# Flipdot_control.net
KiCad netlist of a schematic drawn in EAGLE
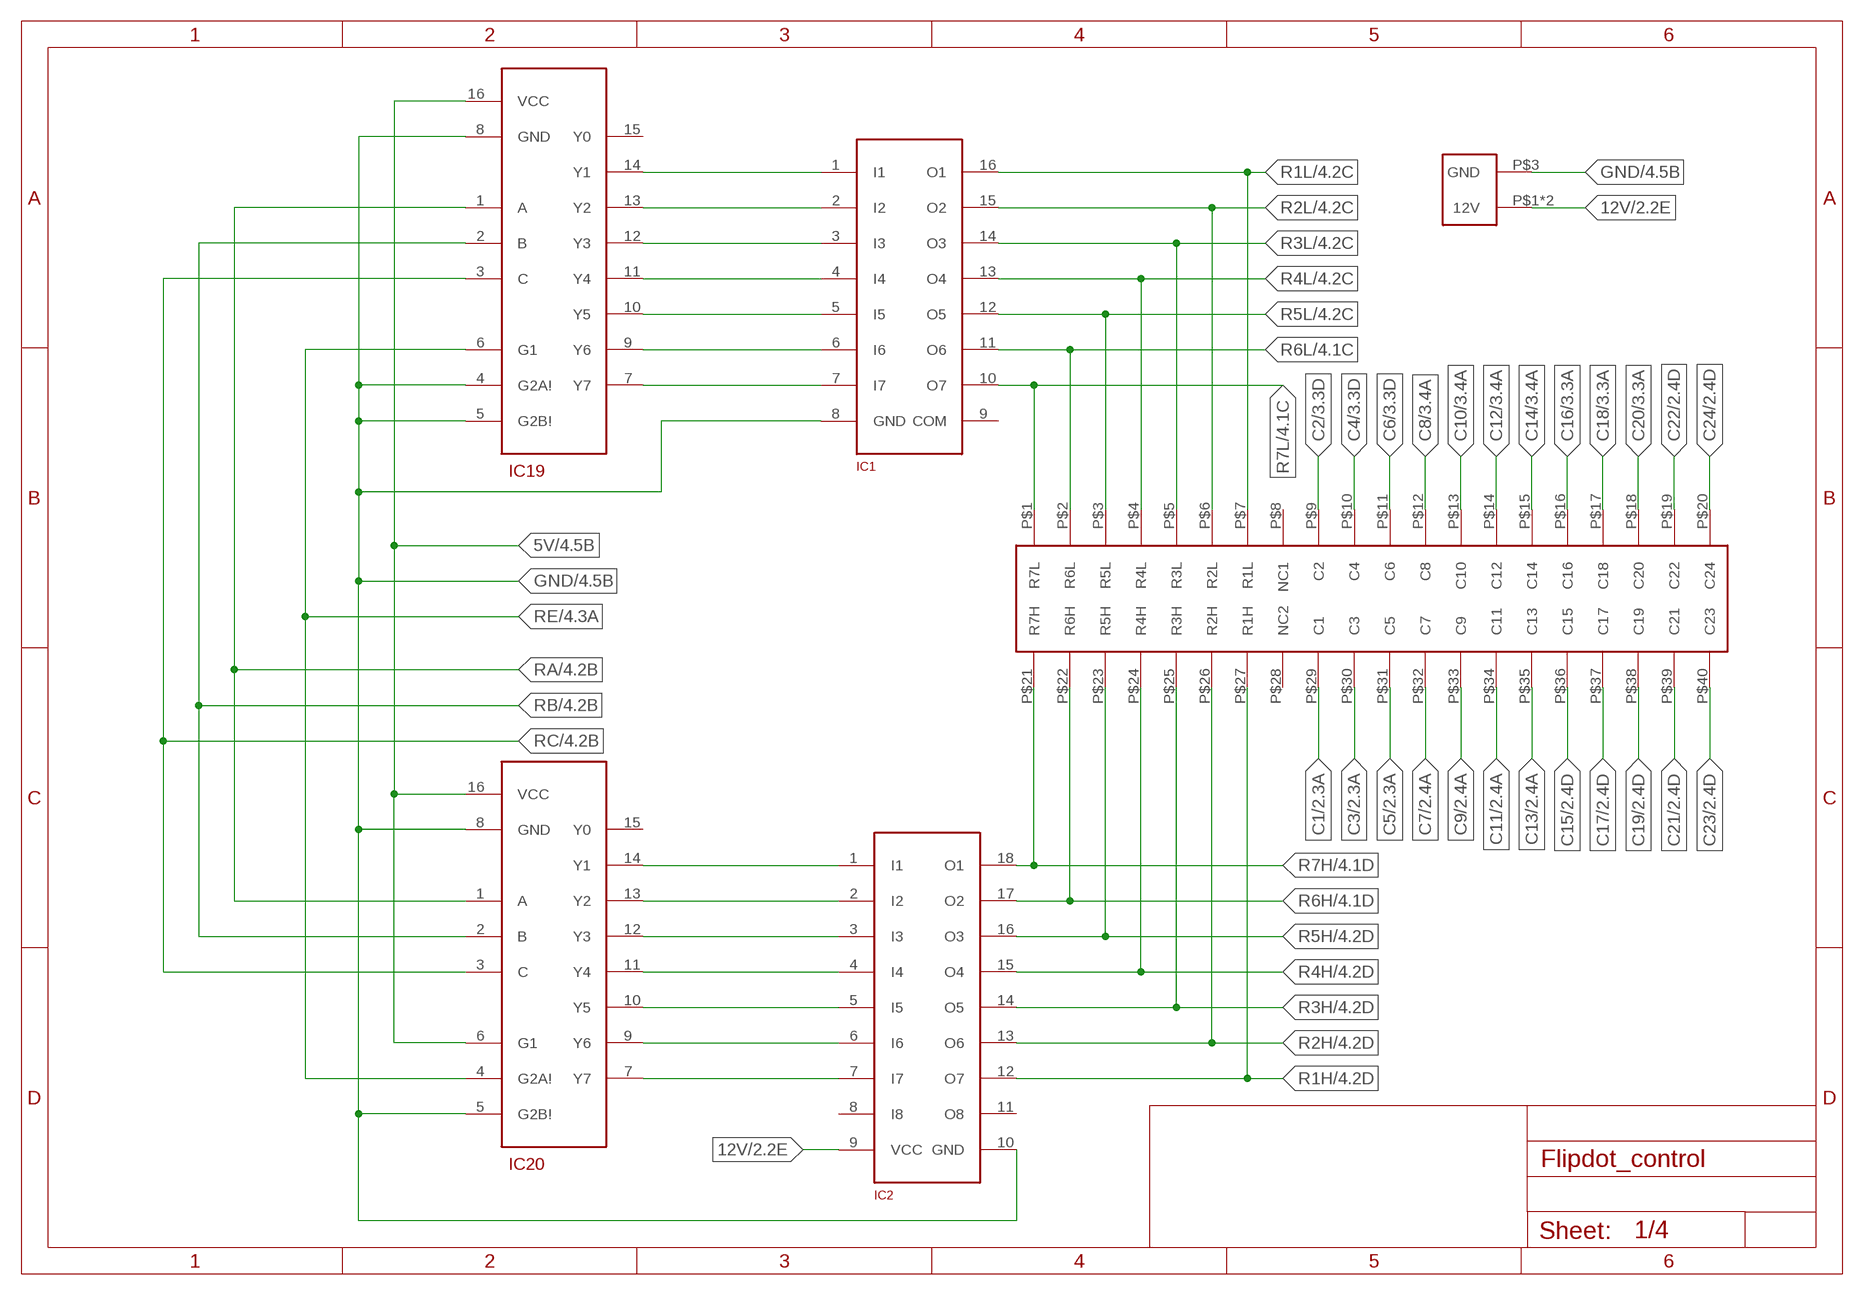
[diagram p0: schematic, sheet 1]
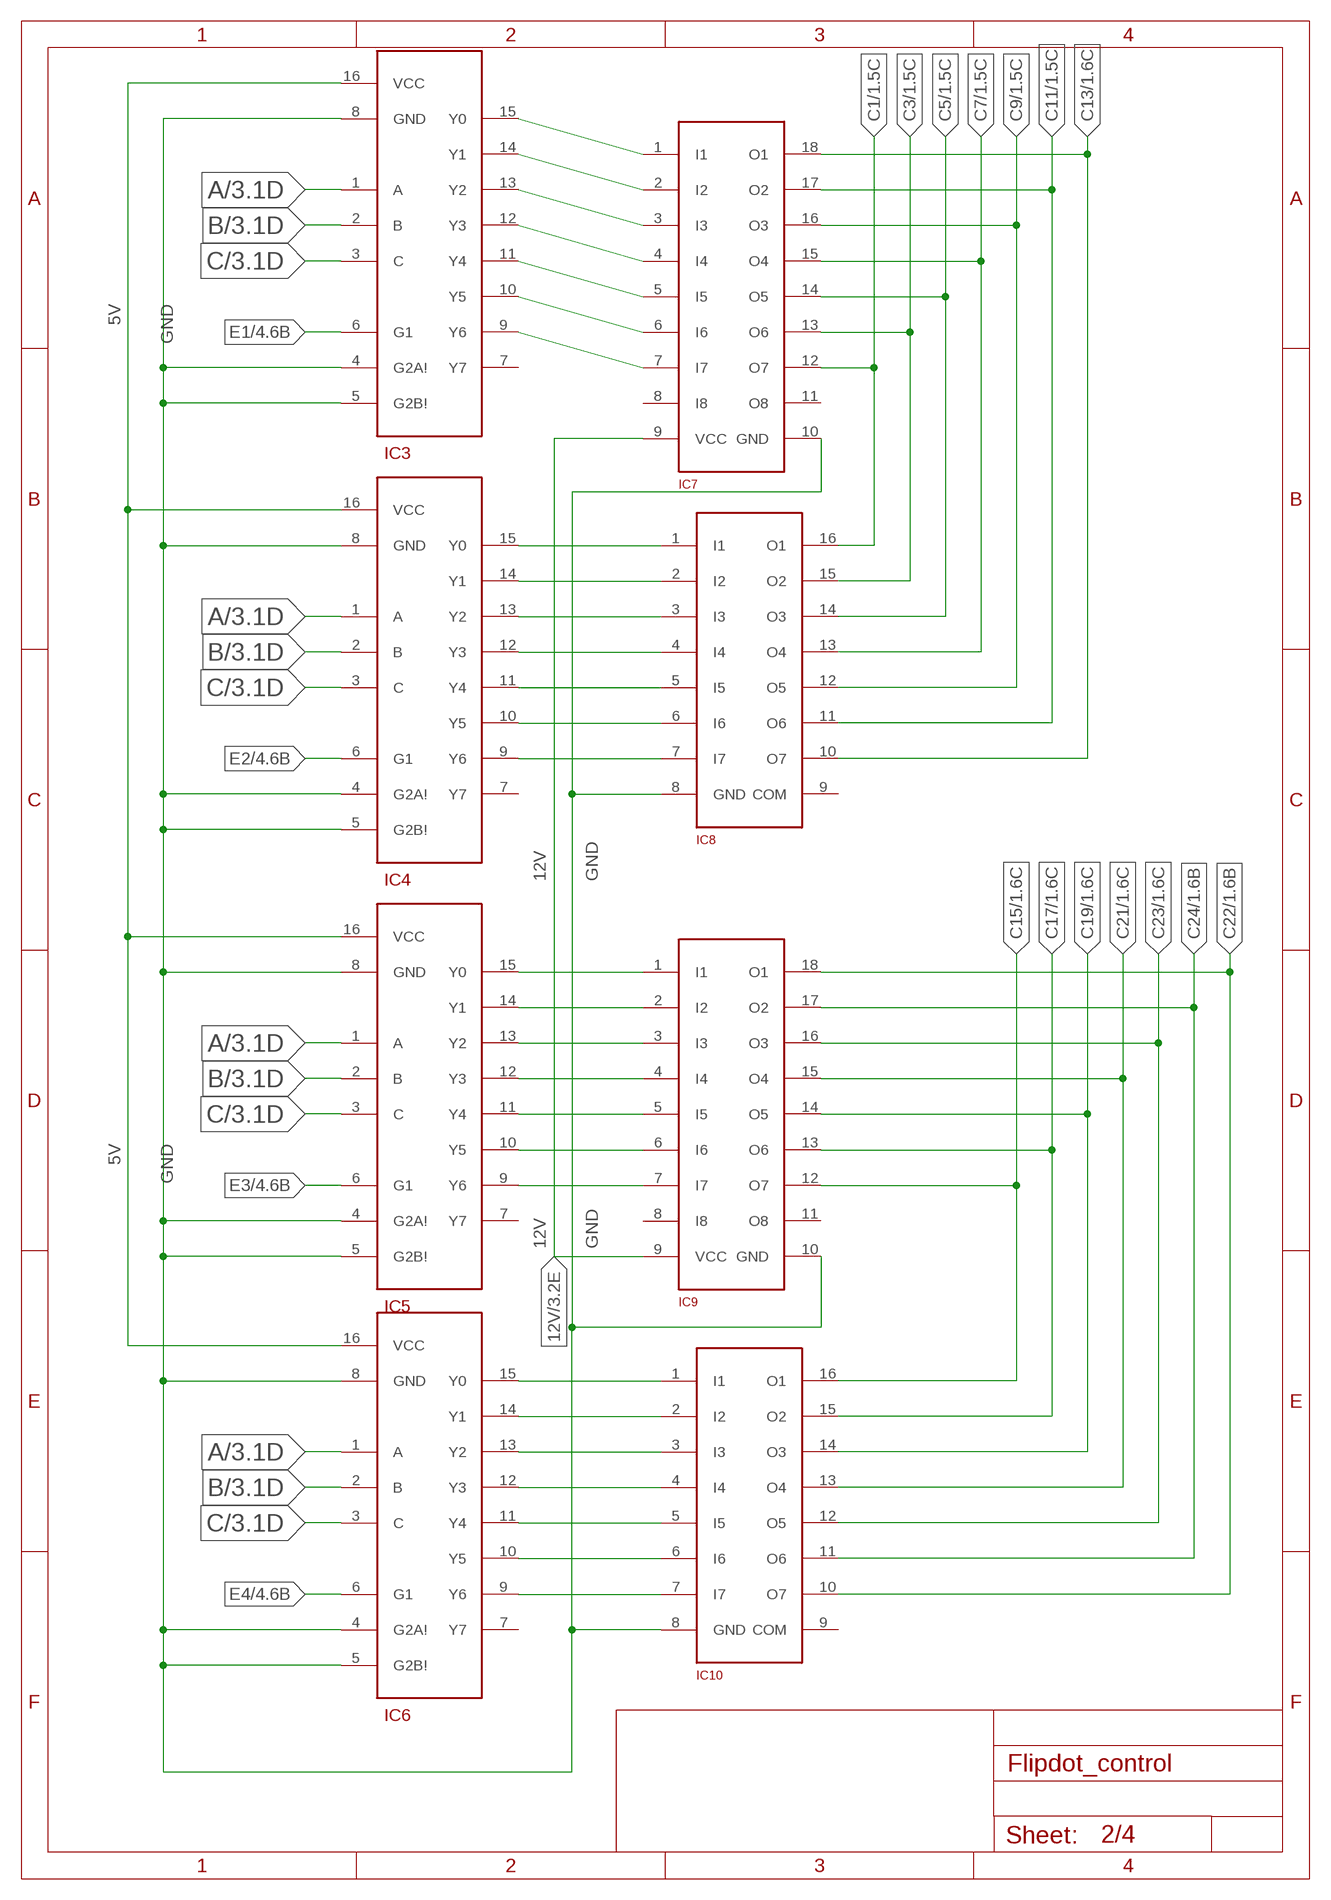
[diagram p1: schematic, sheet 2]
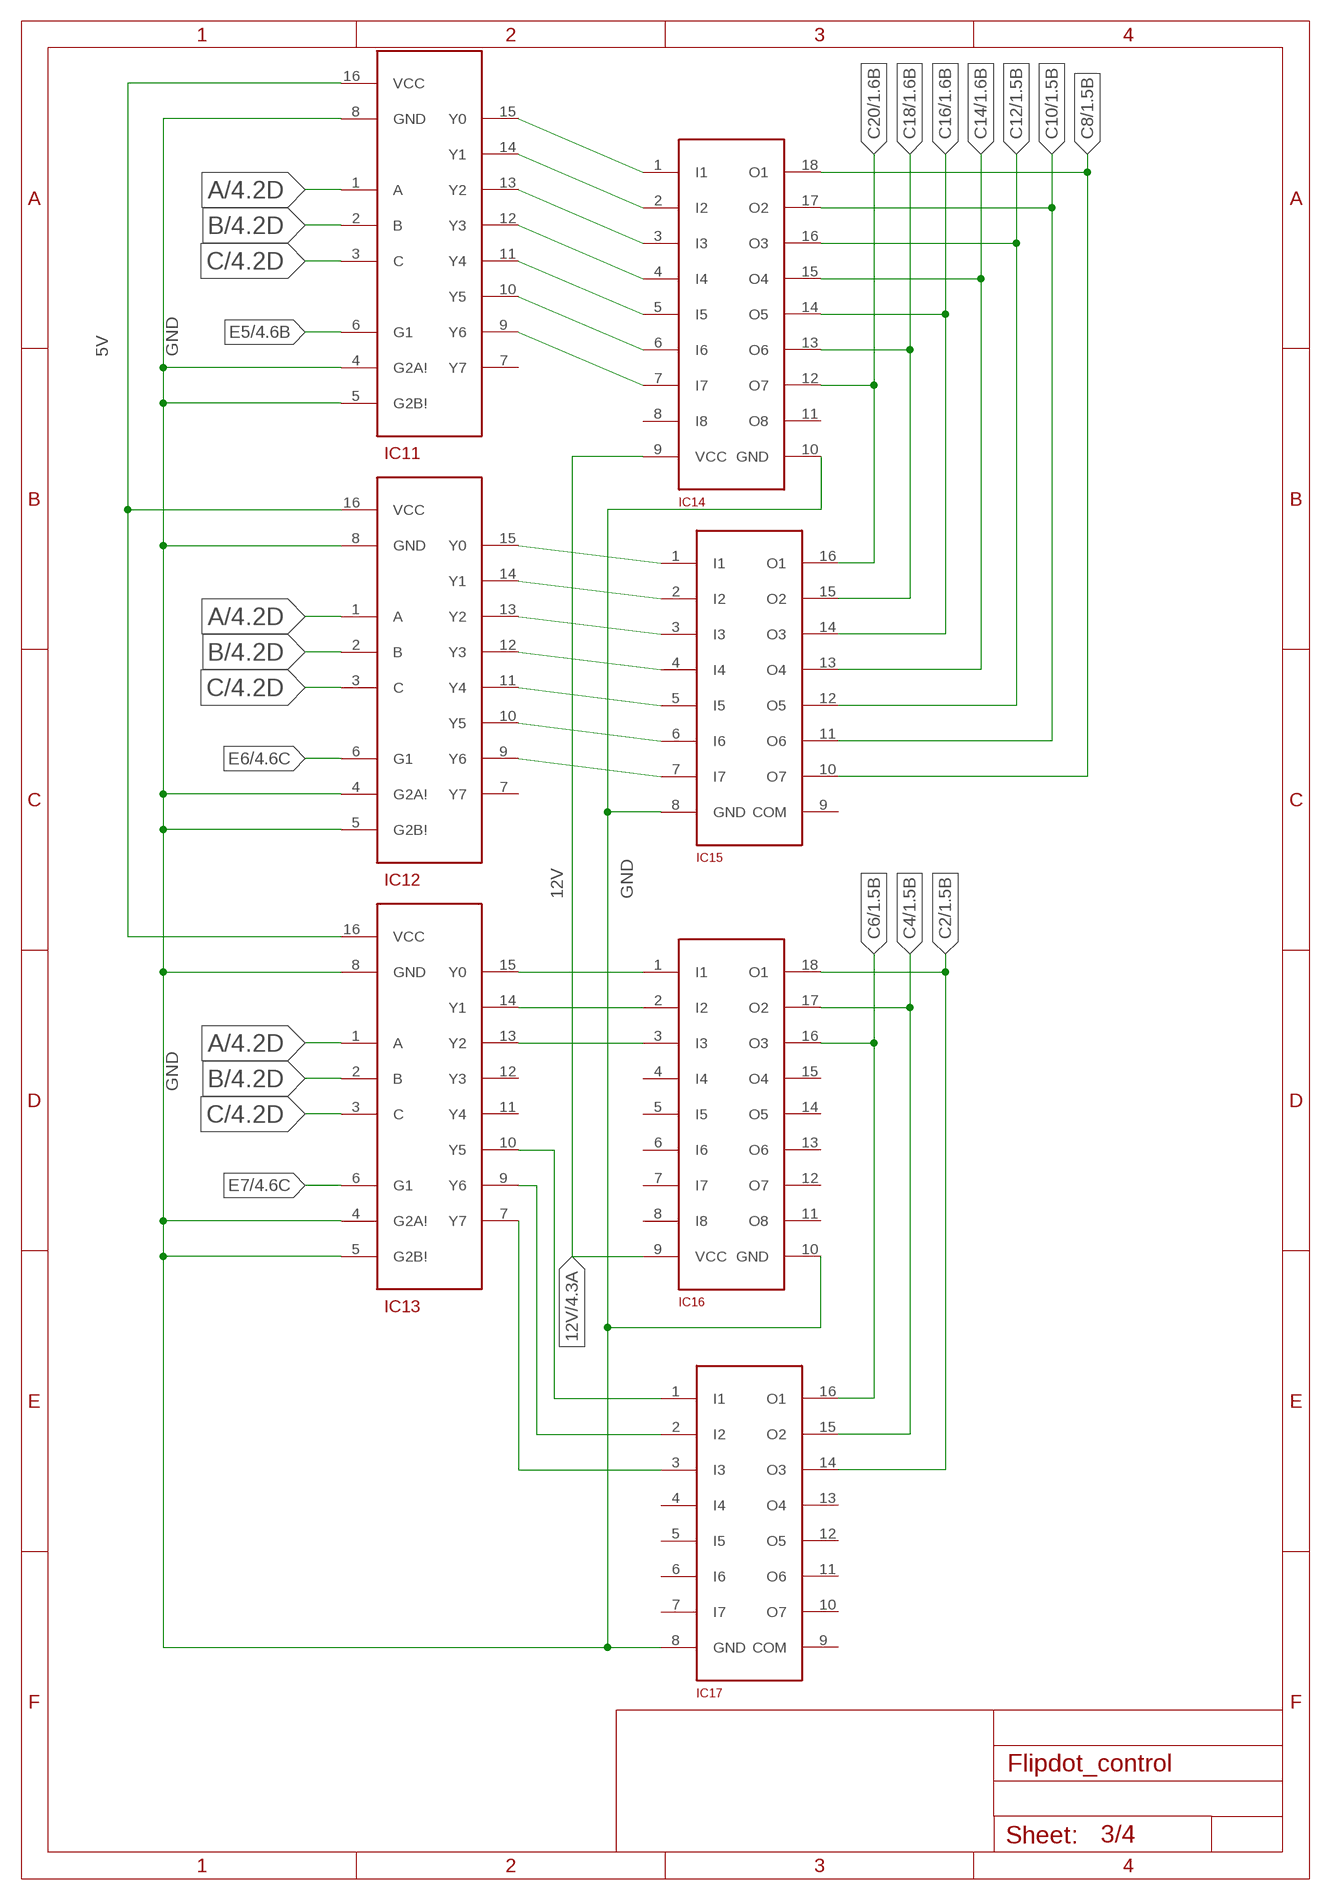
[diagram p2: schematic, sheet 3]
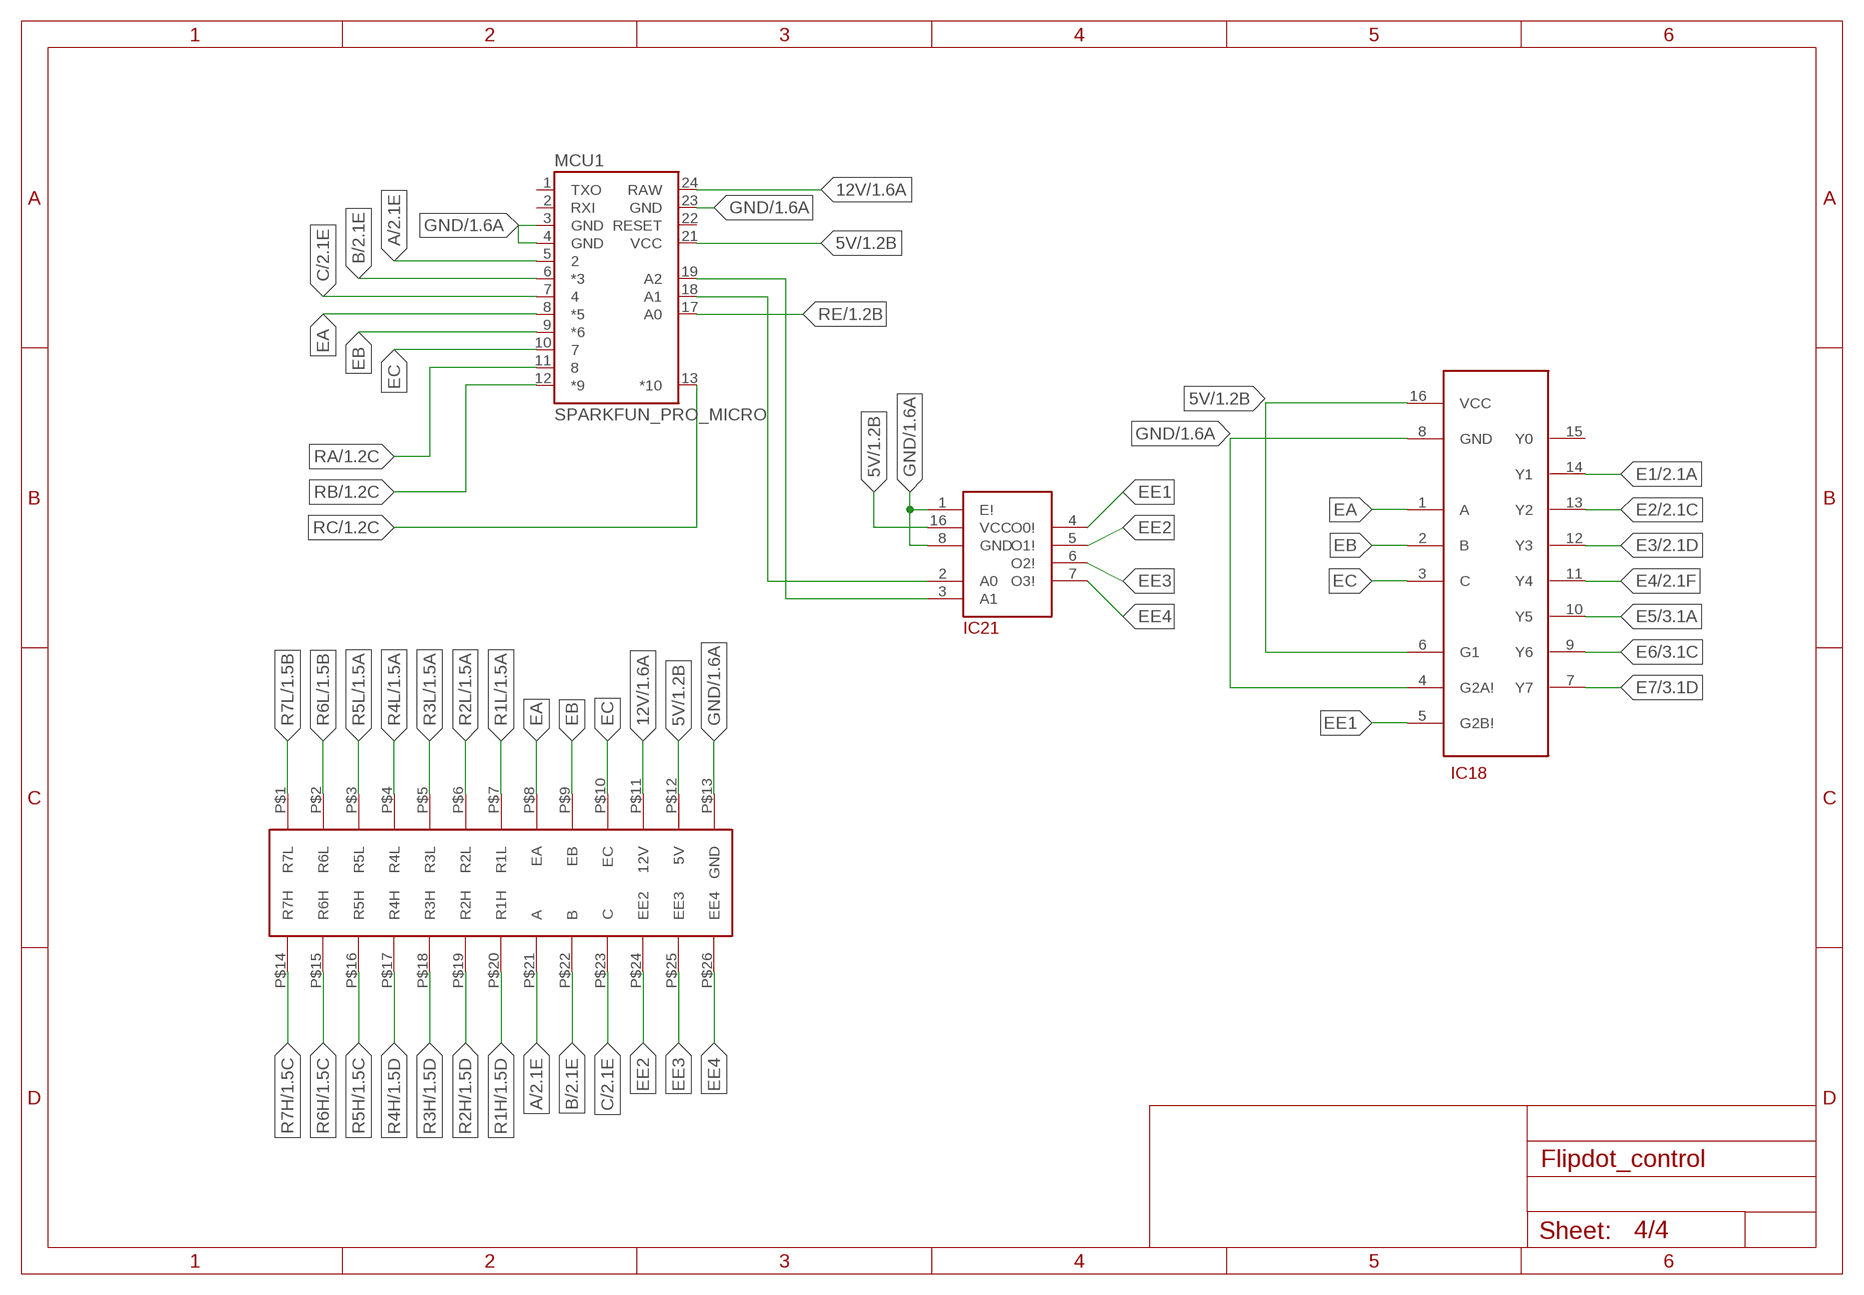
[diagram p3: schematic, sheet 4]

(export (version "E")
  (design (tool "Eeschema 10.0.6"))
  (components
    (comp (ref "IC11")
      (value "M74HC238")
      (footprint "eagle-import:SO16")
      (libsource (lib "eagle-import") (part "M74HC238"))
    )
    (comp (ref "IC12")
      (value "M74HC238")
      (footprint "eagle-import:SO16")
      (libsource (lib "eagle-import") (part "M74HC238"))
    )
    (comp (ref "IC13")
      (value "M74HC238")
      (footprint "eagle-import:SO16")
      (libsource (lib "eagle-import") (part "M74HC238"))
    )
    (comp (ref "IC14")
      (value "TD62783_AFWG")
      (footprint "eagle-import:SO18W")
      (libsource (lib "eagle-import") (part "TD62783_AFWG"))
    )
    (comp (ref "IC15")
      (value "ULN2003")
      (footprint "eagle-import:SO16")
      (libsource (lib "eagle-import") (part "ULN2003"))
    )
    (comp (ref "IC16")
      (value "TD62783_AFWG")
      (footprint "eagle-import:SO18W")
      (libsource (lib "eagle-import") (part "TD62783_AFWG"))
    )
    (comp (ref "IC17")
      (value "ULN2003")
      (footprint "eagle-import:SO16")
      (libsource (lib "eagle-import") (part "ULN2003"))
    )
    (comp (ref "IC1")
      (value "ULN2003")
      (footprint "eagle-import:SO16")
      (libsource (lib "eagle-import") (part "ULN2003"))
    )
    (comp (ref "IC2")
      (value "TD62783_AFWG")
      (footprint "eagle-import:SO18W")
      (libsource (lib "eagle-import") (part "TD62783_AFWG"))
    )
    (comp (ref "IC19")
      (value "M74HC238")
      (footprint "eagle-import:SO16")
      (libsource (lib "eagle-import") (part "M74HC238"))
    )
    (comp (ref "IC20")
      (value "M74HC238")
      (footprint "eagle-import:SO16")
      (libsource (lib "eagle-import") (part "M74HC238"))
    )
    (comp (ref "J1")
      (value "HEADER_40")
      (footprint "eagle-import:HEADER_40")
      (libsource (lib "eagle-import") (part "HEADER_40"))
    )
    (comp (ref "U$1") (value "PS") (footprint "eagle-import:PS") (libsource (lib "eagle-import") (part "PS")))
    (comp (ref "IC18")
      (value "M74HC238")
      (footprint "eagle-import:SO16")
      (libsource (lib "eagle-import") (part "M74HC238"))
    )
    (comp (ref "IC21")
      (value "74AC139SC")
      (footprint "eagle-import:SO16")
      (libsource (lib "eagle-import") (part "74AC139SC"))
    )
    (comp (ref "J2")
      (value "HEADER_26")
      (footprint "eagle-import:HEADER_26")
      (libsource (lib "eagle-import") (part "HEADER_26"))
    )
    (comp (ref "MCU1")
      (value "SPARKFUN_PRO_MICRO")
      (footprint "eagle-import:SPARKFUN_PRO_MICRO")
      (libsource (lib "eagle-import") (part "SPARKFUN_PRO_MICRO"))
    )
    (comp (ref "IC3")
      (value "M74HC238")
      (footprint "eagle-import:SO16")
      (libsource (lib "eagle-import") (part "M74HC238"))
    )
    (comp (ref "IC4")
      (value "M74HC238")
      (footprint "eagle-import:SO16")
      (libsource (lib "eagle-import") (part "M74HC238"))
    )
    (comp (ref "IC5")
      (value "M74HC238")
      (footprint "eagle-import:SO16")
      (libsource (lib "eagle-import") (part "M74HC238"))
    )
    (comp (ref "IC6")
      (value "M74HC238")
      (footprint "eagle-import:SO16")
      (libsource (lib "eagle-import") (part "M74HC238"))
    )
    (comp (ref "IC7")
      (value "TD62783_AFWG")
      (footprint "eagle-import:SO18W")
      (libsource (lib "eagle-import") (part "TD62783_AFWG"))
    )
    (comp (ref "IC8")
      (value "ULN2003")
      (footprint "eagle-import:SO16")
      (libsource (lib "eagle-import") (part "ULN2003"))
    )
    (comp (ref "IC9")
      (value "TD62783_AFWG")
      (footprint "eagle-import:SO18W")
      (libsource (lib "eagle-import") (part "TD62783_AFWG"))
    )
    (comp (ref "IC10")
      (value "ULN2003")
      (footprint "eagle-import:SO16")
      (libsource (lib "eagle-import") (part "ULN2003"))
    )
  )
  (nets
    (net (code "1") (name "5V") (class "Default")
      (node (ref "IC11") (pin "16") (pinfunction "VCC_16") (pintype "bidirectional"))
      (node (ref "IC12") (pin "16") (pinfunction "VCC_16") (pintype "bidirectional"))
      (node (ref "IC13") (pin "16") (pinfunction "VCC_16") (pintype "bidirectional"))
      (node (ref "IC18") (pin "16") (pinfunction "VCC_16") (pintype "bidirectional"))
      (node (ref "IC18") (pin "6") (pinfunction "G1_6") (pintype "bidirectional"))
      (node (ref "IC19") (pin "16") (pinfunction "VCC_16") (pintype "bidirectional"))
      (node (ref "IC20") (pin "16") (pinfunction "VCC_16") (pintype "bidirectional"))
      (node (ref "IC20") (pin "6") (pinfunction "G1_6") (pintype "bidirectional"))
      (node (ref "IC21") (pin "16") (pinfunction "VCC_16") (pintype "bidirectional"))
      (node (ref "IC3") (pin "16") (pinfunction "VCC_16") (pintype "bidirectional"))
      (node (ref "IC4") (pin "16") (pinfunction "VCC_16") (pintype "bidirectional"))
      (node (ref "IC5") (pin "16") (pinfunction "VCC_16") (pintype "bidirectional"))
      (node (ref "IC6") (pin "16") (pinfunction "VCC_16") (pintype "bidirectional"))
      (node (ref "J2") (pin "P$12") (pinfunction "5V_P$12") (pintype "bidirectional"))
      (node (ref "MCU1") (pin "21") (pinfunction "VCC_21") (pintype "power_in"))
    )
    (net (code "2") (name "12V") (class "Default")
      (node (ref "IC14") (pin "9") (pinfunction "VCC_9") (pintype "bidirectional"))
      (node (ref "IC16") (pin "9") (pinfunction "VCC_9") (pintype "bidirectional"))
      (node (ref "IC2") (pin "9") (pinfunction "VCC_9") (pintype "bidirectional"))
      (node (ref "IC7") (pin "9") (pinfunction "VCC_9") (pintype "bidirectional"))
      (node (ref "IC9") (pin "9") (pinfunction "VCC_9") (pintype "bidirectional"))
      (node (ref "J2") (pin "P$11") (pinfunction "12V_P$11") (pintype "bidirectional"))
      (node (ref "MCU1") (pin "24") (pinfunction "RAW_24") (pintype "power_in"))
      (node (ref "U$1") (pin "P$1") (pinfunction "12V_P$1") (pintype "bidirectional"))
      (node (ref "U$1") (pin "P$2") (pinfunction "12V_P$2") (pintype "bidirectional"))
    )
    (net (code "3") (name "A") (class "Default")
      (node (ref "IC11") (pin "1") (pinfunction "A_1") (pintype "bidirectional"))
      (node (ref "IC12") (pin "1") (pinfunction "A_1") (pintype "bidirectional"))
      (node (ref "IC13") (pin "1") (pinfunction "A_1") (pintype "bidirectional"))
      (node (ref "IC3") (pin "1") (pinfunction "A_1") (pintype "bidirectional"))
      (node (ref "IC4") (pin "1") (pinfunction "A_1") (pintype "bidirectional"))
      (node (ref "IC5") (pin "1") (pinfunction "A_1") (pintype "bidirectional"))
      (node (ref "IC6") (pin "1") (pinfunction "A_1") (pintype "bidirectional"))
      (node (ref "J2") (pin "P$21") (pinfunction "A_P$21") (pintype "bidirectional"))
      (node (ref "MCU1") (pin "5") (pinfunction "2_5") (pintype "bidirectional"))
    )
    (net (code "4") (name "B") (class "Default")
      (node (ref "IC11") (pin "2") (pinfunction "B_2") (pintype "bidirectional"))
      (node (ref "IC12") (pin "2") (pinfunction "B_2") (pintype "bidirectional"))
      (node (ref "IC13") (pin "2") (pinfunction "B_2") (pintype "bidirectional"))
      (node (ref "IC3") (pin "2") (pinfunction "B_2") (pintype "bidirectional"))
      (node (ref "IC4") (pin "2") (pinfunction "B_2") (pintype "bidirectional"))
      (node (ref "IC5") (pin "2") (pinfunction "B_2") (pintype "bidirectional"))
      (node (ref "IC6") (pin "2") (pinfunction "B_2") (pintype "bidirectional"))
      (node (ref "J2") (pin "P$22") (pinfunction "B_P$22") (pintype "bidirectional"))
      (node (ref "MCU1") (pin "6") (pinfunction "*3_6") (pintype "bidirectional"))
    )
    (net (code "5") (name "C") (class "Default")
      (node (ref "IC11") (pin "3") (pinfunction "C_3") (pintype "bidirectional"))
      (node (ref "IC12") (pin "3") (pinfunction "C_3") (pintype "bidirectional"))
      (node (ref "IC13") (pin "3") (pinfunction "C_3") (pintype "bidirectional"))
      (node (ref "IC3") (pin "3") (pinfunction "C_3") (pintype "bidirectional"))
      (node (ref "IC4") (pin "3") (pinfunction "C_3") (pintype "bidirectional"))
      (node (ref "IC5") (pin "3") (pinfunction "C_3") (pintype "bidirectional"))
      (node (ref "IC6") (pin "3") (pinfunction "C_3") (pintype "bidirectional"))
      (node (ref "J2") (pin "P$23") (pinfunction "C_P$23") (pintype "bidirectional"))
      (node (ref "MCU1") (pin "7") (pinfunction "4_7") (pintype "bidirectional"))
    )
    (net (code "6") (name "C1") (class "Default")
      (node (ref "IC7") (pin "12") (pinfunction "O7_12") (pintype "bidirectional"))
      (node (ref "IC8") (pin "16") (pinfunction "O1_16") (pintype "bidirectional"))
      (node (ref "J1") (pin "P$29") (pinfunction "C1_P$29") (pintype "bidirectional"))
    )
    (net (code "7") (name "C2") (class "Default")
      (node (ref "IC16") (pin "18") (pinfunction "O1_18") (pintype "bidirectional"))
      (node (ref "IC17") (pin "14") (pinfunction "O3_14") (pintype "bidirectional"))
      (node (ref "J1") (pin "P$9") (pinfunction "C2_P$9") (pintype "bidirectional"))
    )
    (net (code "8") (name "C3") (class "Default")
      (node (ref "IC7") (pin "13") (pinfunction "O6_13") (pintype "bidirectional"))
      (node (ref "IC8") (pin "15") (pinfunction "O2_15") (pintype "bidirectional"))
      (node (ref "J1") (pin "P$30") (pinfunction "C3_P$30") (pintype "bidirectional"))
    )
    (net (code "9") (name "C4") (class "Default")
      (node (ref "IC16") (pin "17") (pinfunction "O2_17") (pintype "bidirectional"))
      (node (ref "IC17") (pin "15") (pinfunction "O2_15") (pintype "bidirectional"))
      (node (ref "J1") (pin "P$10") (pinfunction "C4_P$10") (pintype "bidirectional"))
    )
    (net (code "10") (name "C5") (class "Default")
      (node (ref "IC7") (pin "14") (pinfunction "O5_14") (pintype "bidirectional"))
      (node (ref "IC8") (pin "14") (pinfunction "O3_14") (pintype "bidirectional"))
      (node (ref "J1") (pin "P$31") (pinfunction "C5_P$31") (pintype "bidirectional"))
    )
    (net (code "11") (name "C6") (class "Default")
      (node (ref "IC16") (pin "16") (pinfunction "O3_16") (pintype "bidirectional"))
      (node (ref "IC17") (pin "16") (pinfunction "O1_16") (pintype "bidirectional"))
      (node (ref "J1") (pin "P$11") (pinfunction "C6_P$11") (pintype "bidirectional"))
    )
    (net (code "12") (name "C7") (class "Default")
      (node (ref "IC7") (pin "15") (pinfunction "O4_15") (pintype "bidirectional"))
      (node (ref "IC8") (pin "13") (pinfunction "O4_13") (pintype "bidirectional"))
      (node (ref "J1") (pin "P$32") (pinfunction "C7_P$32") (pintype "bidirectional"))
    )
    (net (code "13") (name "C8") (class "Default")
      (node (ref "IC14") (pin "18") (pinfunction "O1_18") (pintype "bidirectional"))
      (node (ref "IC15") (pin "10") (pinfunction "O7_10") (pintype "bidirectional"))
      (node (ref "J1") (pin "P$12") (pinfunction "C8_P$12") (pintype "bidirectional"))
    )
    (net (code "14") (name "C9") (class "Default")
      (node (ref "IC7") (pin "16") (pinfunction "O3_16") (pintype "bidirectional"))
      (node (ref "IC8") (pin "12") (pinfunction "O5_12") (pintype "bidirectional"))
      (node (ref "J1") (pin "P$33") (pinfunction "C9_P$33") (pintype "bidirectional"))
    )
    (net (code "15") (name "C10") (class "Default")
      (node (ref "IC14") (pin "17") (pinfunction "O2_17") (pintype "bidirectional"))
      (node (ref "IC15") (pin "11") (pinfunction "O6_11") (pintype "bidirectional"))
      (node (ref "J1") (pin "P$13") (pinfunction "C10_P$13") (pintype "bidirectional"))
    )
    (net (code "16") (name "C11") (class "Default")
      (node (ref "IC7") (pin "17") (pinfunction "O2_17") (pintype "bidirectional"))
      (node (ref "IC8") (pin "11") (pinfunction "O6_11") (pintype "bidirectional"))
      (node (ref "J1") (pin "P$34") (pinfunction "C11_P$34") (pintype "bidirectional"))
    )
    (net (code "17") (name "C12") (class "Default")
      (node (ref "IC14") (pin "16") (pinfunction "O3_16") (pintype "bidirectional"))
      (node (ref "IC15") (pin "12") (pinfunction "O5_12") (pintype "bidirectional"))
      (node (ref "J1") (pin "P$14") (pinfunction "C12_P$14") (pintype "bidirectional"))
    )
    (net (code "18") (name "C13") (class "Default")
      (node (ref "IC7") (pin "18") (pinfunction "O1_18") (pintype "bidirectional"))
      (node (ref "IC8") (pin "10") (pinfunction "O7_10") (pintype "bidirectional"))
      (node (ref "J1") (pin "P$35") (pinfunction "C13_P$35") (pintype "bidirectional"))
    )
    (net (code "19") (name "C14") (class "Default")
      (node (ref "IC14") (pin "15") (pinfunction "O4_15") (pintype "bidirectional"))
      (node (ref "IC15") (pin "13") (pinfunction "O4_13") (pintype "bidirectional"))
      (node (ref "J1") (pin "P$15") (pinfunction "C14_P$15") (pintype "bidirectional"))
    )
    (net (code "20") (name "C15") (class "Default")
      (node (ref "IC10") (pin "16") (pinfunction "O1_16") (pintype "bidirectional"))
      (node (ref "IC9") (pin "12") (pinfunction "O7_12") (pintype "bidirectional"))
      (node (ref "J1") (pin "P$36") (pinfunction "C15_P$36") (pintype "bidirectional"))
    )
    (net (code "21") (name "C16") (class "Default")
      (node (ref "IC14") (pin "14") (pinfunction "O5_14") (pintype "bidirectional"))
      (node (ref "IC15") (pin "14") (pinfunction "O3_14") (pintype "bidirectional"))
      (node (ref "J1") (pin "P$16") (pinfunction "C16_P$16") (pintype "bidirectional"))
    )
    (net (code "22") (name "C17") (class "Default")
      (node (ref "IC10") (pin "15") (pinfunction "O2_15") (pintype "bidirectional"))
      (node (ref "IC9") (pin "13") (pinfunction "O6_13") (pintype "bidirectional"))
      (node (ref "J1") (pin "P$37") (pinfunction "C17_P$37") (pintype "bidirectional"))
    )
    (net (code "23") (name "C18") (class "Default")
      (node (ref "IC14") (pin "13") (pinfunction "O6_13") (pintype "bidirectional"))
      (node (ref "IC15") (pin "15") (pinfunction "O2_15") (pintype "bidirectional"))
      (node (ref "J1") (pin "P$17") (pinfunction "C18_P$17") (pintype "bidirectional"))
    )
    (net (code "24") (name "C19") (class "Default")
      (node (ref "IC10") (pin "14") (pinfunction "O3_14") (pintype "bidirectional"))
      (node (ref "IC9") (pin "14") (pinfunction "O5_14") (pintype "bidirectional"))
      (node (ref "J1") (pin "P$38") (pinfunction "C19_P$38") (pintype "bidirectional"))
    )
    (net (code "25") (name "C20") (class "Default")
      (node (ref "IC14") (pin "12") (pinfunction "O7_12") (pintype "bidirectional"))
      (node (ref "IC15") (pin "16") (pinfunction "O1_16") (pintype "bidirectional"))
      (node (ref "J1") (pin "P$18") (pinfunction "C20_P$18") (pintype "bidirectional"))
    )
    (net (code "26") (name "C21") (class "Default")
      (node (ref "IC10") (pin "13") (pinfunction "O4_13") (pintype "bidirectional"))
      (node (ref "IC9") (pin "15") (pinfunction "O4_15") (pintype "bidirectional"))
      (node (ref "J1") (pin "P$39") (pinfunction "C21_P$39") (pintype "bidirectional"))
    )
    (net (code "27") (name "C22") (class "Default")
      (node (ref "IC10") (pin "10") (pinfunction "O7_10") (pintype "bidirectional"))
      (node (ref "IC9") (pin "18") (pinfunction "O1_18") (pintype "bidirectional"))
      (node (ref "J1") (pin "P$19") (pinfunction "C22_P$19") (pintype "bidirectional"))
    )
    (net (code "28") (name "C23") (class "Default")
      (node (ref "IC10") (pin "12") (pinfunction "O5_12") (pintype "bidirectional"))
      (node (ref "IC9") (pin "16") (pinfunction "O3_16") (pintype "bidirectional"))
      (node (ref "J1") (pin "P$40") (pinfunction "C23_P$40") (pintype "bidirectional"))
    )
    (net (code "29") (name "C24") (class "Default")
      (node (ref "IC10") (pin "11") (pinfunction "O6_11") (pintype "bidirectional"))
      (node (ref "IC9") (pin "17") (pinfunction "O2_17") (pintype "bidirectional"))
      (node (ref "J1") (pin "P$20") (pinfunction "C24_P$20") (pintype "bidirectional"))
    )
    (net (code "30") (name "E1") (class "Default")
      (node (ref "IC18") (pin "14") (pinfunction "Y1_14") (pintype "bidirectional"))
      (node (ref "IC3") (pin "6") (pinfunction "G1_6") (pintype "bidirectional"))
    )
    (net (code "31") (name "E2") (class "Default")
      (node (ref "IC18") (pin "13") (pinfunction "Y2_13") (pintype "bidirectional"))
      (node (ref "IC4") (pin "6") (pinfunction "G1_6") (pintype "bidirectional"))
    )
    (net (code "32") (name "E3") (class "Default")
      (node (ref "IC18") (pin "12") (pinfunction "Y3_12") (pintype "bidirectional"))
      (node (ref "IC5") (pin "6") (pinfunction "G1_6") (pintype "bidirectional"))
    )
    (net (code "33") (name "E4") (class "Default")
      (node (ref "IC18") (pin "11") (pinfunction "Y4_11") (pintype "bidirectional"))
      (node (ref "IC6") (pin "6") (pinfunction "G1_6") (pintype "bidirectional"))
    )
    (net (code "34") (name "E5") (class "Default")
      (node (ref "IC11") (pin "6") (pinfunction "G1_6") (pintype "bidirectional"))
      (node (ref "IC18") (pin "10") (pinfunction "Y5_10") (pintype "bidirectional"))
    )
    (net (code "35") (name "E6") (class "Default")
      (node (ref "IC12") (pin "6") (pinfunction "G1_6") (pintype "bidirectional"))
      (node (ref "IC18") (pin "9") (pinfunction "Y6_9") (pintype "bidirectional"))
    )
    (net (code "36") (name "E7") (class "Default")
      (node (ref "IC13") (pin "6") (pinfunction "G1_6") (pintype "bidirectional"))
      (node (ref "IC18") (pin "7") (pinfunction "Y7_7") (pintype "bidirectional"))
    )
    (net (code "37") (name "EA") (class "Default")
      (node (ref "IC18") (pin "1") (pinfunction "A_1") (pintype "bidirectional"))
      (node (ref "J2") (pin "P$8") (pinfunction "EA_P$8") (pintype "bidirectional"))
      (node (ref "MCU1") (pin "8") (pinfunction "*5_8") (pintype "bidirectional"))
    )
    (net (code "38") (name "EB") (class "Default")
      (node (ref "IC18") (pin "2") (pinfunction "B_2") (pintype "bidirectional"))
      (node (ref "J2") (pin "P$9") (pinfunction "EB_P$9") (pintype "bidirectional"))
      (node (ref "MCU1") (pin "9") (pinfunction "*6_9") (pintype "bidirectional"))
    )
    (net (code "39") (name "EC") (class "Default")
      (node (ref "IC18") (pin "3") (pinfunction "C_3") (pintype "bidirectional"))
      (node (ref "J2") (pin "P$10") (pinfunction "EC_P$10") (pintype "bidirectional"))
      (node (ref "MCU1") (pin "10") (pinfunction "7_10") (pintype "bidirectional"))
    )
    (net (code "40") (name "EE1") (class "Default")
      (node (ref "IC18") (pin "5") (pinfunction "G2B~{}_5") (pintype "bidirectional"))
      (node (ref "IC21") (pin "4") (pinfunction "O0~{}_4") (pintype "bidirectional"))
    )
    (net (code "41") (name "EE2") (class "Default")
      (node (ref "IC21") (pin "5") (pinfunction "O1~{}_5") (pintype "bidirectional"))
      (node (ref "J2") (pin "P$24") (pinfunction "EE2_P$24") (pintype "bidirectional"))
    )
    (net (code "42") (name "EE3") (class "Default")
      (node (ref "IC21") (pin "6") (pinfunction "O2~{}_6") (pintype "bidirectional"))
      (node (ref "J2") (pin "P$25") (pinfunction "EE3_P$25") (pintype "bidirectional"))
    )
    (net (code "43") (name "EE4") (class "Default")
      (node (ref "IC21") (pin "7") (pinfunction "O3~{}_7") (pintype "bidirectional"))
      (node (ref "J2") (pin "P$26") (pinfunction "EE4_P$26") (pintype "bidirectional"))
    )
    (net (code "44") (name "GND") (class "Default")
      (node (ref "IC1") (pin "8") (pinfunction "GND_8") (pintype "bidirectional"))
      (node (ref "IC10") (pin "8") (pinfunction "GND_8") (pintype "bidirectional"))
      (node (ref "IC11") (pin "4") (pinfunction "G2A~{}_4") (pintype "bidirectional"))
      (node (ref "IC11") (pin "5") (pinfunction "G2B~{}_5") (pintype "bidirectional"))
      (node (ref "IC11") (pin "8") (pinfunction "GND_8") (pintype "bidirectional"))
      (node (ref "IC12") (pin "4") (pinfunction "G2A~{}_4") (pintype "bidirectional"))
      (node (ref "IC12") (pin "5") (pinfunction "G2B~{}_5") (pintype "bidirectional"))
      (node (ref "IC12") (pin "8") (pinfunction "GND_8") (pintype "bidirectional"))
      (node (ref "IC13") (pin "4") (pinfunction "G2A~{}_4") (pintype "bidirectional"))
      (node (ref "IC13") (pin "5") (pinfunction "G2B~{}_5") (pintype "bidirectional"))
      (node (ref "IC13") (pin "8") (pinfunction "GND_8") (pintype "bidirectional"))
      (node (ref "IC14") (pin "10") (pinfunction "GND_10") (pintype "bidirectional"))
      (node (ref "IC15") (pin "8") (pinfunction "GND_8") (pintype "bidirectional"))
      (node (ref "IC16") (pin "10") (pinfunction "GND_10") (pintype "bidirectional"))
      (node (ref "IC17") (pin "8") (pinfunction "GND_8") (pintype "bidirectional"))
      (node (ref "IC18") (pin "4") (pinfunction "G2A~{}_4") (pintype "bidirectional"))
      (node (ref "IC18") (pin "8") (pinfunction "GND_8") (pintype "bidirectional"))
      (node (ref "IC19") (pin "4") (pinfunction "G2A~{}_4") (pintype "bidirectional"))
      (node (ref "IC19") (pin "5") (pinfunction "G2B~{}_5") (pintype "bidirectional"))
      (node (ref "IC19") (pin "8") (pinfunction "GND_8") (pintype "bidirectional"))
      (node (ref "IC2") (pin "10") (pinfunction "GND_10") (pintype "bidirectional"))
      (node (ref "IC20") (pin "5") (pinfunction "G2B~{}_5") (pintype "bidirectional"))
      (node (ref "IC20") (pin "8") (pinfunction "GND_8") (pintype "bidirectional"))
      (node (ref "IC21") (pin "1") (pinfunction "E~{}_1") (pintype "bidirectional"))
      (node (ref "IC21") (pin "8") (pinfunction "GND_8") (pintype "bidirectional"))
      (node (ref "IC3") (pin "4") (pinfunction "G2A~{}_4") (pintype "bidirectional"))
      (node (ref "IC3") (pin "5") (pinfunction "G2B~{}_5") (pintype "bidirectional"))
      (node (ref "IC3") (pin "8") (pinfunction "GND_8") (pintype "bidirectional"))
      (node (ref "IC4") (pin "4") (pinfunction "G2A~{}_4") (pintype "bidirectional"))
      (node (ref "IC4") (pin "5") (pinfunction "G2B~{}_5") (pintype "bidirectional"))
      (node (ref "IC4") (pin "8") (pinfunction "GND_8") (pintype "bidirectional"))
      (node (ref "IC5") (pin "4") (pinfunction "G2A~{}_4") (pintype "bidirectional"))
      (node (ref "IC5") (pin "5") (pinfunction "G2B~{}_5") (pintype "bidirectional"))
      (node (ref "IC5") (pin "8") (pinfunction "GND_8") (pintype "bidirectional"))
      (node (ref "IC6") (pin "4") (pinfunction "G2A~{}_4") (pintype "bidirectional"))
      (node (ref "IC6") (pin "5") (pinfunction "G2B~{}_5") (pintype "bidirectional"))
      (node (ref "IC6") (pin "8") (pinfunction "GND_8") (pintype "bidirectional"))
      (node (ref "IC7") (pin "10") (pinfunction "GND_10") (pintype "bidirectional"))
      (node (ref "IC8") (pin "8") (pinfunction "GND_8") (pintype "bidirectional"))
      (node (ref "IC9") (pin "10") (pinfunction "GND_10") (pintype "bidirectional"))
      (node (ref "J2") (pin "P$13") (pinfunction "GND_P$13") (pintype "bidirectional"))
      (node (ref "MCU1") (pin "23") (pinfunction "GND_23") (pintype "power_in"))
      (node (ref "MCU1") (pin "3") (pinfunction "GND_3") (pintype "power_in"))
      (node (ref "MCU1") (pin "4") (pinfunction "GND_4") (pintype "power_in"))
      (node (ref "U$1") (pin "P$3") (pinfunction "GND_P$3") (pintype "bidirectional"))
    )
    (net (code "45") (name "Net-(IC1-I1)") (class "Default")
      (node (ref "IC1") (pin "1") (pinfunction "I1_1") (pintype "bidirectional"))
      (node (ref "IC19") (pin "14") (pinfunction "Y1_14") (pintype "bidirectional"))
    )
    (net (code "46") (name "Net-(IC1-I2)") (class "Default")
      (node (ref "IC1") (pin "2") (pinfunction "I2_2") (pintype "bidirectional"))
      (node (ref "IC19") (pin "13") (pinfunction "Y2_13") (pintype "bidirectional"))
    )
    (net (code "47") (name "Net-(IC1-I3)") (class "Default")
      (node (ref "IC1") (pin "3") (pinfunction "I3_3") (pintype "bidirectional"))
      (node (ref "IC19") (pin "12") (pinfunction "Y3_12") (pintype "bidirectional"))
    )
    (net (code "48") (name "Net-(IC1-I4)") (class "Default")
      (node (ref "IC1") (pin "4") (pinfunction "I4_4") (pintype "bidirectional"))
      (node (ref "IC19") (pin "11") (pinfunction "Y4_11") (pintype "bidirectional"))
    )
    (net (code "49") (name "Net-(IC1-I5)") (class "Default")
      (node (ref "IC1") (pin "5") (pinfunction "I5_5") (pintype "bidirectional"))
      (node (ref "IC19") (pin "10") (pinfunction "Y5_10") (pintype "bidirectional"))
    )
    (net (code "50") (name "Net-(IC1-I6)") (class "Default")
      (node (ref "IC1") (pin "6") (pinfunction "I6_6") (pintype "bidirectional"))
      (node (ref "IC19") (pin "9") (pinfunction "Y6_9") (pintype "bidirectional"))
    )
    (net (code "51") (name "Net-(IC1-I7)") (class "Default")
      (node (ref "IC1") (pin "7") (pinfunction "I7_7") (pintype "bidirectional"))
      (node (ref "IC19") (pin "7") (pinfunction "Y7_7") (pintype "bidirectional"))
    )
    (net (code "52") (name "Net-(IC2-I1)") (class "Default")
      (node (ref "IC2") (pin "1") (pinfunction "I1_1") (pintype "bidirectional"))
      (node (ref "IC20") (pin "14") (pinfunction "Y1_14") (pintype "bidirectional"))
    )
    (net (code "53") (name "Net-(IC2-I2)") (class "Default")
      (node (ref "IC2") (pin "2") (pinfunction "I2_2") (pintype "bidirectional"))
      (node (ref "IC20") (pin "13") (pinfunction "Y2_13") (pintype "bidirectional"))
    )
    (net (code "54") (name "Net-(IC2-I3)") (class "Default")
      (node (ref "IC2") (pin "3") (pinfunction "I3_3") (pintype "bidirectional"))
      (node (ref "IC20") (pin "12") (pinfunction "Y3_12") (pintype "bidirectional"))
    )
    (net (code "55") (name "Net-(IC2-I4)") (class "Default")
      (node (ref "IC2") (pin "4") (pinfunction "I4_4") (pintype "bidirectional"))
      (node (ref "IC20") (pin "11") (pinfunction "Y4_11") (pintype "bidirectional"))
    )
    (net (code "56") (name "Net-(IC2-I5)") (class "Default")
      (node (ref "IC2") (pin "5") (pinfunction "I5_5") (pintype "bidirectional"))
      (node (ref "IC20") (pin "10") (pinfunction "Y5_10") (pintype "bidirectional"))
    )
    (net (code "57") (name "Net-(IC2-I6)") (class "Default")
      (node (ref "IC2") (pin "6") (pinfunction "I6_6") (pintype "bidirectional"))
      (node (ref "IC20") (pin "9") (pinfunction "Y6_9") (pintype "bidirectional"))
    )
    (net (code "58") (name "Net-(IC2-I7)") (class "Default")
      (node (ref "IC2") (pin "7") (pinfunction "I7_7") (pintype "bidirectional"))
      (node (ref "IC20") (pin "7") (pinfunction "Y7_7") (pintype "bidirectional"))
    )
    (net (code "59") (name "Net-(IC3-Y0)") (class "Default")
      (node (ref "IC3") (pin "15") (pinfunction "Y0_15") (pintype "bidirectional"))
      (node (ref "IC7") (pin "1") (pinfunction "I1_1") (pintype "bidirectional"))
    )
    (net (code "60") (name "Net-(IC3-Y1)") (class "Default")
      (node (ref "IC3") (pin "14") (pinfunction "Y1_14") (pintype "bidirectional"))
      (node (ref "IC7") (pin "2") (pinfunction "I2_2") (pintype "bidirectional"))
    )
    (net (code "61") (name "Net-(IC3-Y2)") (class "Default")
      (node (ref "IC3") (pin "13") (pinfunction "Y2_13") (pintype "bidirectional"))
      (node (ref "IC7") (pin "3") (pinfunction "I3_3") (pintype "bidirectional"))
    )
    (net (code "62") (name "Net-(IC3-Y3)") (class "Default")
      (node (ref "IC3") (pin "12") (pinfunction "Y3_12") (pintype "bidirectional"))
      (node (ref "IC7") (pin "4") (pinfunction "I4_4") (pintype "bidirectional"))
    )
    (net (code "63") (name "Net-(IC3-Y4)") (class "Default")
      (node (ref "IC3") (pin "11") (pinfunction "Y4_11") (pintype "bidirectional"))
      (node (ref "IC7") (pin "5") (pinfunction "I5_5") (pintype "bidirectional"))
    )
    (net (code "64") (name "Net-(IC3-Y5)") (class "Default")
      (node (ref "IC3") (pin "10") (pinfunction "Y5_10") (pintype "bidirectional"))
      (node (ref "IC7") (pin "6") (pinfunction "I6_6") (pintype "bidirectional"))
    )
    (net (code "65") (name "Net-(IC3-Y6)") (class "Default")
      (node (ref "IC3") (pin "9") (pinfunction "Y6_9") (pintype "bidirectional"))
      (node (ref "IC7") (pin "7") (pinfunction "I7_7") (pintype "bidirectional"))
    )
    (net (code "66") (name "Net-(IC4-Y0)") (class "Default")
      (node (ref "IC4") (pin "15") (pinfunction "Y0_15") (pintype "bidirectional"))
      (node (ref "IC8") (pin "1") (pinfunction "I1_1") (pintype "bidirectional"))
    )
    (net (code "67") (name "Net-(IC4-Y1)") (class "Default")
      (node (ref "IC4") (pin "14") (pinfunction "Y1_14") (pintype "bidirectional"))
      (node (ref "IC8") (pin "2") (pinfunction "I2_2") (pintype "bidirectional"))
    )
    (net (code "68") (name "Net-(IC4-Y2)") (class "Default")
      (node (ref "IC4") (pin "13") (pinfunction "Y2_13") (pintype "bidirectional"))
      (node (ref "IC8") (pin "3") (pinfunction "I3_3") (pintype "bidirectional"))
    )
    (net (code "69") (name "Net-(IC4-Y3)") (class "Default")
      (node (ref "IC4") (pin "12") (pinfunction "Y3_12") (pintype "bidirectional"))
      (node (ref "IC8") (pin "4") (pinfunction "I4_4") (pintype "bidirectional"))
    )
    (net (code "70") (name "Net-(IC4-Y4)") (class "Default")
      (node (ref "IC4") (pin "11") (pinfunction "Y4_11") (pintype "bidirectional"))
      (node (ref "IC8") (pin "5") (pinfunction "I5_5") (pintype "bidirectional"))
    )
    (net (code "71") (name "Net-(IC4-Y5)") (class "Default")
      (node (ref "IC4") (pin "10") (pinfunction "Y5_10") (pintype "bidirectional"))
      (node (ref "IC8") (pin "6") (pinfunction "I6_6") (pintype "bidirectional"))
    )
    (net (code "72") (name "Net-(IC4-Y6)") (class "Default")
      (node (ref "IC4") (pin "9") (pinfunction "Y6_9") (pintype "bidirectional"))
      (node (ref "IC8") (pin "7") (pinfunction "I7_7") (pintype "bidirectional"))
    )
    (net (code "73") (name "Net-(IC5-Y0)") (class "Default")
      (node (ref "IC5") (pin "15") (pinfunction "Y0_15") (pintype "bidirectional"))
      (node (ref "IC9") (pin "1") (pinfunction "I1_1") (pintype "bidirectional"))
    )
    (net (code "74") (name "Net-(IC5-Y1)") (class "Default")
      (node (ref "IC5") (pin "14") (pinfunction "Y1_14") (pintype "bidirectional"))
      (node (ref "IC9") (pin "2") (pinfunction "I2_2") (pintype "bidirectional"))
    )
    (net (code "75") (name "Net-(IC5-Y2)") (class "Default")
      (node (ref "IC5") (pin "13") (pinfunction "Y2_13") (pintype "bidirectional"))
      (node (ref "IC9") (pin "3") (pinfunction "I3_3") (pintype "bidirectional"))
    )
    (net (code "76") (name "Net-(IC5-Y3)") (class "Default")
      (node (ref "IC5") (pin "12") (pinfunction "Y3_12") (pintype "bidirectional"))
      (node (ref "IC9") (pin "4") (pinfunction "I4_4") (pintype "bidirectional"))
    )
    (net (code "77") (name "Net-(IC5-Y4)") (class "Default")
      (node (ref "IC5") (pin "11") (pinfunction "Y4_11") (pintype "bidirectional"))
      (node (ref "IC9") (pin "5") (pinfunction "I5_5") (pintype "bidirectional"))
    )
    (net (code "78") (name "Net-(IC5-Y5)") (class "Default")
      (node (ref "IC5") (pin "10") (pinfunction "Y5_10") (pintype "bidirectional"))
      (node (ref "IC9") (pin "6") (pinfunction "I6_6") (pintype "bidirectional"))
    )
    (net (code "79") (name "Net-(IC5-Y6)") (class "Default")
      (node (ref "IC5") (pin "9") (pinfunction "Y6_9") (pintype "bidirectional"))
      (node (ref "IC9") (pin "7") (pinfunction "I7_7") (pintype "bidirectional"))
    )
    (net (code "80") (name "Net-(IC10-I1)") (class "Default")
      (node (ref "IC10") (pin "1") (pinfunction "I1_1") (pintype "bidirectional"))
      (node (ref "IC6") (pin "15") (pinfunction "Y0_15") (pintype "bidirectional"))
    )
    (net (code "81") (name "Net-(IC10-I2)") (class "Default")
      (node (ref "IC10") (pin "2") (pinfunction "I2_2") (pintype "bidirectional"))
      (node (ref "IC6") (pin "14") (pinfunction "Y1_14") (pintype "bidirectional"))
    )
    (net (code "82") (name "Net-(IC10-I3)") (class "Default")
      (node (ref "IC10") (pin "3") (pinfunction "I3_3") (pintype "bidirectional"))
      (node (ref "IC6") (pin "13") (pinfunction "Y2_13") (pintype "bidirectional"))
    )
    (net (code "83") (name "Net-(IC10-I4)") (class "Default")
      (node (ref "IC10") (pin "4") (pinfunction "I4_4") (pintype "bidirectional"))
      (node (ref "IC6") (pin "12") (pinfunction "Y3_12") (pintype "bidirectional"))
    )
    (net (code "84") (name "Net-(IC10-I5)") (class "Default")
      (node (ref "IC10") (pin "5") (pinfunction "I5_5") (pintype "bidirectional"))
      (node (ref "IC6") (pin "11") (pinfunction "Y4_11") (pintype "bidirectional"))
    )
    (net (code "85") (name "Net-(IC10-I6)") (class "Default")
      (node (ref "IC10") (pin "6") (pinfunction "I6_6") (pintype "bidirectional"))
      (node (ref "IC6") (pin "10") (pinfunction "Y5_10") (pintype "bidirectional"))
    )
    (net (code "86") (name "Net-(IC10-I7)") (class "Default")
      (node (ref "IC10") (pin "7") (pinfunction "I7_7") (pintype "bidirectional"))
      (node (ref "IC6") (pin "9") (pinfunction "Y6_9") (pintype "bidirectional"))
    )
    (net (code "87") (name "Net-(IC11-Y0)") (class "Default")
      (node (ref "IC11") (pin "15") (pinfunction "Y0_15") (pintype "bidirectional"))
      (node (ref "IC14") (pin "1") (pinfunction "I1_1") (pintype "bidirectional"))
    )
    (net (code "88") (name "Net-(IC11-Y1)") (class "Default")
      (node (ref "IC11") (pin "14") (pinfunction "Y1_14") (pintype "bidirectional"))
      (node (ref "IC14") (pin "2") (pinfunction "I2_2") (pintype "bidirectional"))
    )
    (net (code "89") (name "Net-(IC11-Y2)") (class "Default")
      (node (ref "IC11") (pin "13") (pinfunction "Y2_13") (pintype "bidirectional"))
      (node (ref "IC14") (pin "3") (pinfunction "I3_3") (pintype "bidirectional"))
    )
    (net (code "90") (name "Net-(IC11-Y3)") (class "Default")
      (node (ref "IC11") (pin "12") (pinfunction "Y3_12") (pintype "bidirectional"))
      (node (ref "IC14") (pin "4") (pinfunction "I4_4") (pintype "bidirectional"))
    )
    (net (code "91") (name "Net-(IC11-Y4)") (class "Default")
      (node (ref "IC11") (pin "11") (pinfunction "Y4_11") (pintype "bidirectional"))
      (node (ref "IC14") (pin "5") (pinfunction "I5_5") (pintype "bidirectional"))
    )
    (net (code "92") (name "Net-(IC11-Y5)") (class "Default")
      (node (ref "IC11") (pin "10") (pinfunction "Y5_10") (pintype "bidirectional"))
      (node (ref "IC14") (pin "6") (pinfunction "I6_6") (pintype "bidirectional"))
    )
    (net (code "93") (name "Net-(IC11-Y6)") (class "Default")
      (node (ref "IC11") (pin "9") (pinfunction "Y6_9") (pintype "bidirectional"))
      (node (ref "IC14") (pin "7") (pinfunction "I7_7") (pintype "bidirectional"))
    )
    (net (code "94") (name "Net-(IC12-Y0)") (class "Default")
      (node (ref "IC12") (pin "15") (pinfunction "Y0_15") (pintype "bidirectional"))
      (node (ref "IC15") (pin "1") (pinfunction "I1_1") (pintype "bidirectional"))
    )
    (net (code "95") (name "Net-(IC12-Y1)") (class "Default")
      (node (ref "IC12") (pin "14") (pinfunction "Y1_14") (pintype "bidirectional"))
      (node (ref "IC15") (pin "2") (pinfunction "I2_2") (pintype "bidirectional"))
    )
    (net (code "96") (name "Net-(IC12-Y2)") (class "Default")
      (node (ref "IC12") (pin "13") (pinfunction "Y2_13") (pintype "bidirectional"))
      (node (ref "IC15") (pin "3") (pinfunction "I3_3") (pintype "bidirectional"))
    )
    (net (code "97") (name "Net-(IC12-Y3)") (class "Default")
      (node (ref "IC12") (pin "12") (pinfunction "Y3_12") (pintype "bidirectional"))
      (node (ref "IC15") (pin "4") (pinfunction "I4_4") (pintype "bidirectional"))
    )
    (net (code "98") (name "Net-(IC12-Y4)") (class "Default")
      (node (ref "IC12") (pin "11") (pinfunction "Y4_11") (pintype "bidirectional"))
      (node (ref "IC15") (pin "5") (pinfunction "I5_5") (pintype "bidirectional"))
    )
    (net (code "99") (name "Net-(IC12-Y5)") (class "Default")
      (node (ref "IC12") (pin "10") (pinfunction "Y5_10") (pintype "bidirectional"))
      (node (ref "IC15") (pin "6") (pinfunction "I6_6") (pintype "bidirectional"))
    )
    (net (code "100") (name "Net-(IC12-Y6)") (class "Default")
      (node (ref "IC12") (pin "9") (pinfunction "Y6_9") (pintype "bidirectional"))
      (node (ref "IC15") (pin "7") (pinfunction "I7_7") (pintype "bidirectional"))
    )
    (net (code "101") (name "Net-(IC13-Y0)") (class "Default")
      (node (ref "IC13") (pin "15") (pinfunction "Y0_15") (pintype "bidirectional"))
      (node (ref "IC16") (pin "1") (pinfunction "I1_1") (pintype "bidirectional"))
    )
    (net (code "102") (name "Net-(IC13-Y1)") (class "Default")
      (node (ref "IC13") (pin "14") (pinfunction "Y1_14") (pintype "bidirectional"))
      (node (ref "IC16") (pin "2") (pinfunction "I2_2") (pintype "bidirectional"))
    )
    (net (code "103") (name "Net-(IC13-Y2)") (class "Default")
      (node (ref "IC13") (pin "13") (pinfunction "Y2_13") (pintype "bidirectional"))
      (node (ref "IC16") (pin "3") (pinfunction "I3_3") (pintype "bidirectional"))
    )
    (net (code "104") (name "Net-(IC13-Y5)") (class "Default")
      (node (ref "IC13") (pin "10") (pinfunction "Y5_10") (pintype "bidirectional"))
      (node (ref "IC17") (pin "1") (pinfunction "I1_1") (pintype "bidirectional"))
    )
    (net (code "105") (name "Net-(IC13-Y6)") (class "Default")
      (node (ref "IC13") (pin "9") (pinfunction "Y6_9") (pintype "bidirectional"))
      (node (ref "IC17") (pin "2") (pinfunction "I2_2") (pintype "bidirectional"))
    )
    (net (code "106") (name "Net-(IC13-Y7)") (class "Default")
      (node (ref "IC13") (pin "7") (pinfunction "Y7_7") (pintype "bidirectional"))
      (node (ref "IC17") (pin "3") (pinfunction "I3_3") (pintype "bidirectional"))
    )
    (net (code "107") (name "Net-(IC21-A0)") (class "Default")
      (node (ref "IC21") (pin "2") (pinfunction "A0_2") (pintype "bidirectional"))
      (node (ref "MCU1") (pin "18") (pinfunction "A1_18") (pintype "bidirectional"))
    )
    (net (code "108") (name "Net-(IC21-A1)") (class "Default")
      (node (ref "IC21") (pin "3") (pinfunction "A1_3") (pintype "bidirectional"))
      (node (ref "MCU1") (pin "19") (pinfunction "A2_19") (pintype "bidirectional"))
    )
    (net (code "109") (name "R1H") (class "Default")
      (node (ref "IC2") (pin "12") (pinfunction "O7_12") (pintype "bidirectional"))
      (node (ref "J1") (pin "P$27") (pinfunction "R1H_P$27") (pintype "bidirectional"))
      (node (ref "J2") (pin "P$20") (pinfunction "R1H_P$20") (pintype "bidirectional"))
    )
    (net (code "110") (name "R1L") (class "Default")
      (node (ref "IC1") (pin "16") (pinfunction "O1_16") (pintype "bidirectional"))
      (node (ref "J1") (pin "P$7") (pinfunction "R1L_P$7") (pintype "bidirectional"))
      (node (ref "J2") (pin "P$7") (pinfunction "R1L_P$7") (pintype "bidirectional"))
    )
    (net (code "111") (name "R2H") (class "Default")
      (node (ref "IC2") (pin "13") (pinfunction "O6_13") (pintype "bidirectional"))
      (node (ref "J1") (pin "P$26") (pinfunction "R2H_P$26") (pintype "bidirectional"))
      (node (ref "J2") (pin "P$19") (pinfunction "R2H_P$19") (pintype "bidirectional"))
    )
    (net (code "112") (name "R2L") (class "Default")
      (node (ref "IC1") (pin "15") (pinfunction "O2_15") (pintype "bidirectional"))
      (node (ref "J1") (pin "P$6") (pinfunction "R2L_P$6") (pintype "bidirectional"))
      (node (ref "J2") (pin "P$6") (pinfunction "R2L_P$6") (pintype "bidirectional"))
    )
    (net (code "113") (name "R3H") (class "Default")
      (node (ref "IC2") (pin "14") (pinfunction "O5_14") (pintype "bidirectional"))
      (node (ref "J1") (pin "P$25") (pinfunction "R3H_P$25") (pintype "bidirectional"))
      (node (ref "J2") (pin "P$18") (pinfunction "R3H_P$18") (pintype "bidirectional"))
    )
    (net (code "114") (name "R3L") (class "Default")
      (node (ref "IC1") (pin "14") (pinfunction "O3_14") (pintype "bidirectional"))
      (node (ref "J1") (pin "P$5") (pinfunction "R3L_P$5") (pintype "bidirectional"))
      (node (ref "J2") (pin "P$5") (pinfunction "R3L_P$5") (pintype "bidirectional"))
    )
    (net (code "115") (name "R4H") (class "Default")
      (node (ref "IC2") (pin "15") (pinfunction "O4_15") (pintype "bidirectional"))
      (node (ref "J1") (pin "P$24") (pinfunction "R4H_P$24") (pintype "bidirectional"))
      (node (ref "J2") (pin "P$17") (pinfunction "R4H_P$17") (pintype "bidirectional"))
    )
    (net (code "116") (name "R4L") (class "Default")
      (node (ref "IC1") (pin "13") (pinfunction "O4_13") (pintype "bidirectional"))
      (node (ref "J1") (pin "P$4") (pinfunction "R4L_P$4") (pintype "bidirectional"))
      (node (ref "J2") (pin "P$4") (pinfunction "R4L_P$4") (pintype "bidirectional"))
    )
    (net (code "117") (name "R5H") (class "Default")
      (node (ref "IC2") (pin "16") (pinfunction "O3_16") (pintype "bidirectional"))
      (node (ref "J1") (pin "P$23") (pinfunction "R5H_P$23") (pintype "bidirectional"))
      (node (ref "J2") (pin "P$16") (pinfunction "R5H_P$16") (pintype "bidirectional"))
    )
    (net (code "118") (name "R5L") (class "Default")
      (node (ref "IC1") (pin "12") (pinfunction "O5_12") (pintype "bidirectional"))
      (node (ref "J1") (pin "P$3") (pinfunction "R5L_P$3") (pintype "bidirectional"))
      (node (ref "J2") (pin "P$3") (pinfunction "R5L_P$3") (pintype "bidirectional"))
    )
    (net (code "119") (name "R6H") (class "Default")
      (node (ref "IC2") (pin "17") (pinfunction "O2_17") (pintype "bidirectional"))
      (node (ref "J1") (pin "P$22") (pinfunction "R6H_P$22") (pintype "bidirectional"))
      (node (ref "J2") (pin "P$15") (pinfunction "R6H_P$15") (pintype "bidirectional"))
    )
    (net (code "120") (name "R6L") (class "Default")
      (node (ref "IC1") (pin "11") (pinfunction "O6_11") (pintype "bidirectional"))
      (node (ref "J1") (pin "P$2") (pinfunction "R6L_P$2") (pintype "bidirectional"))
      (node (ref "J2") (pin "P$2") (pinfunction "R6L_P$2") (pintype "bidirectional"))
    )
    (net (code "121") (name "R7H") (class "Default")
      (node (ref "IC2") (pin "18") (pinfunction "O1_18") (pintype "bidirectional"))
      (node (ref "J1") (pin "P$21") (pinfunction "R7H_P$21") (pintype "bidirectional"))
      (node (ref "J2") (pin "P$14") (pinfunction "R7H_P$14") (pintype "bidirectional"))
    )
    (net (code "122") (name "R7L") (class "Default")
      (node (ref "IC1") (pin "10") (pinfunction "O7_10") (pintype "bidirectional"))
      (node (ref "J1") (pin "P$1") (pinfunction "R7L_P$1") (pintype "bidirectional"))
      (node (ref "J2") (pin "P$1") (pinfunction "R7L_P$1") (pintype "bidirectional"))
    )
    (net (code "123") (name "RA") (class "Default")
      (node (ref "IC19") (pin "1") (pinfunction "A_1") (pintype "bidirectional"))
      (node (ref "IC20") (pin "1") (pinfunction "A_1") (pintype "bidirectional"))
      (node (ref "MCU1") (pin "11") (pinfunction "8_11") (pintype "bidirectional"))
    )
    (net (code "124") (name "RB") (class "Default")
      (node (ref "IC19") (pin "2") (pinfunction "B_2") (pintype "bidirectional"))
      (node (ref "IC20") (pin "2") (pinfunction "B_2") (pintype "bidirectional"))
      (node (ref "MCU1") (pin "12") (pinfunction "*9_12") (pintype "bidirectional"))
    )
    (net (code "125") (name "RC") (class "Default")
      (node (ref "IC19") (pin "3") (pinfunction "C_3") (pintype "bidirectional"))
      (node (ref "IC20") (pin "3") (pinfunction "C_3") (pintype "bidirectional"))
      (node (ref "MCU1") (pin "13") (pinfunction "*10_13") (pintype "bidirectional"))
    )
    (net (code "126") (name "RE") (class "Default")
      (node (ref "IC19") (pin "6") (pinfunction "G1_6") (pintype "bidirectional"))
      (node (ref "IC20") (pin "4") (pinfunction "G2A~{}_4") (pintype "bidirectional"))
      (node (ref "MCU1") (pin "17") (pinfunction "A0_17") (pintype "bidirectional"))
    )
    (net (code "127") (name "unconnected-(IC1-COM-Pad9)") (class "Default")
      (node (ref "IC1") (pin "9") (pinfunction "COM_9") (pintype "bidirectional"))
    )
    (net (code "128") (name "unconnected-(IC2-I8-Pad8)") (class "Default")
      (node (ref "IC2") (pin "8") (pinfunction "I8_8") (pintype "bidirectional"))
    )
    (net (code "129") (name "unconnected-(IC2-O8-Pad11)") (class "Default")
      (node (ref "IC2") (pin "11") (pinfunction "O8_11") (pintype "bidirectional"))
    )
    (net (code "130") (name "unconnected-(IC3-Y7-Pad7)") (class "Default")
      (node (ref "IC3") (pin "7") (pinfunction "Y7_7") (pintype "bidirectional"))
    )
    (net (code "131") (name "unconnected-(IC4-Y7-Pad7)") (class "Default")
      (node (ref "IC4") (pin "7") (pinfunction "Y7_7") (pintype "bidirectional"))
    )
    (net (code "132") (name "unconnected-(IC5-Y7-Pad7)") (class "Default")
      (node (ref "IC5") (pin "7") (pinfunction "Y7_7") (pintype "bidirectional"))
    )
    (net (code "133") (name "unconnected-(IC6-Y7-Pad7)") (class "Default")
      (node (ref "IC6") (pin "7") (pinfunction "Y7_7") (pintype "bidirectional"))
    )
    (net (code "134") (name "unconnected-(IC7-I8-Pad8)") (class "Default")
      (node (ref "IC7") (pin "8") (pinfunction "I8_8") (pintype "bidirectional"))
    )
    (net (code "135") (name "unconnected-(IC7-O8-Pad11)") (class "Default")
      (node (ref "IC7") (pin "11") (pinfunction "O8_11") (pintype "bidirectional"))
    )
    (net (code "136") (name "unconnected-(IC8-COM-Pad9)") (class "Default")
      (node (ref "IC8") (pin "9") (pinfunction "COM_9") (pintype "bidirectional"))
    )
    (net (code "137") (name "unconnected-(IC9-I8-Pad8)") (class "Default")
      (node (ref "IC9") (pin "8") (pinfunction "I8_8") (pintype "bidirectional"))
    )
    (net (code "138") (name "unconnected-(IC9-O8-Pad11)") (class "Default")
      (node (ref "IC9") (pin "11") (pinfunction "O8_11") (pintype "bidirectional"))
    )
    (net (code "139") (name "unconnected-(IC10-COM-Pad9)") (class "Default")
      (node (ref "IC10") (pin "9") (pinfunction "COM_9") (pintype "bidirectional"))
    )
    (net (code "140") (name "unconnected-(IC11-Y7-Pad7)") (class "Default")
      (node (ref "IC11") (pin "7") (pinfunction "Y7_7") (pintype "bidirectional"))
    )
    (net (code "141") (name "unconnected-(IC12-Y7-Pad7)") (class "Default")
      (node (ref "IC12") (pin "7") (pinfunction "Y7_7") (pintype "bidirectional"))
    )
    (net (code "142") (name "unconnected-(IC13-Y3-Pad12)") (class "Default")
      (node (ref "IC13") (pin "12") (pinfunction "Y3_12") (pintype "bidirectional"))
    )
    (net (code "143") (name "unconnected-(IC13-Y4-Pad11)") (class "Default")
      (node (ref "IC13") (pin "11") (pinfunction "Y4_11") (pintype "bidirectional"))
    )
    (net (code "144") (name "unconnected-(IC14-I8-Pad8)") (class "Default")
      (node (ref "IC14") (pin "8") (pinfunction "I8_8") (pintype "bidirectional"))
    )
    (net (code "145") (name "unconnected-(IC14-O8-Pad11)") (class "Default")
      (node (ref "IC14") (pin "11") (pinfunction "O8_11") (pintype "bidirectional"))
    )
    (net (code "146") (name "unconnected-(IC15-COM-Pad9)") (class "Default")
      (node (ref "IC15") (pin "9") (pinfunction "COM_9") (pintype "bidirectional"))
    )
    (net (code "147") (name "unconnected-(IC16-I4-Pad4)") (class "Default")
      (node (ref "IC16") (pin "4") (pinfunction "I4_4") (pintype "bidirectional"))
    )
    (net (code "148") (name "unconnected-(IC16-I5-Pad5)") (class "Default")
      (node (ref "IC16") (pin "5") (pinfunction "I5_5") (pintype "bidirectional"))
    )
    (net (code "149") (name "unconnected-(IC16-I6-Pad6)") (class "Default")
      (node (ref "IC16") (pin "6") (pinfunction "I6_6") (pintype "bidirectional"))
    )
    (net (code "150") (name "unconnected-(IC16-I7-Pad7)") (class "Default")
      (node (ref "IC16") (pin "7") (pinfunction "I7_7") (pintype "bidirectional"))
    )
    (net (code "151") (name "unconnected-(IC16-I8-Pad8)") (class "Default")
      (node (ref "IC16") (pin "8") (pinfunction "I8_8") (pintype "bidirectional"))
    )
    (net (code "152") (name "unconnected-(IC16-O4-Pad15)") (class "Default")
      (node (ref "IC16") (pin "15") (pinfunction "O4_15") (pintype "bidirectional"))
    )
    (net (code "153") (name "unconnected-(IC16-O5-Pad14)") (class "Default")
      (node (ref "IC16") (pin "14") (pinfunction "O5_14") (pintype "bidirectional"))
    )
    (net (code "154") (name "unconnected-(IC16-O6-Pad13)") (class "Default")
      (node (ref "IC16") (pin "13") (pinfunction "O6_13") (pintype "bidirectional"))
    )
    (net (code "155") (name "unconnected-(IC16-O7-Pad12)") (class "Default")
      (node (ref "IC16") (pin "12") (pinfunction "O7_12") (pintype "bidirectional"))
    )
    (net (code "156") (name "unconnected-(IC16-O8-Pad11)") (class "Default")
      (node (ref "IC16") (pin "11") (pinfunction "O8_11") (pintype "bidirectional"))
    )
    (net (code "157") (name "unconnected-(IC17-COM-Pad9)") (class "Default")
      (node (ref "IC17") (pin "9") (pinfunction "COM_9") (pintype "bidirectional"))
    )
    (net (code "158") (name "unconnected-(IC17-I4-Pad4)") (class "Default")
      (node (ref "IC17") (pin "4") (pinfunction "I4_4") (pintype "bidirectional"))
    )
    (net (code "159") (name "unconnected-(IC17-I5-Pad5)") (class "Default")
      (node (ref "IC17") (pin "5") (pinfunction "I5_5") (pintype "bidirectional"))
    )
    (net (code "160") (name "unconnected-(IC17-I6-Pad6)") (class "Default")
      (node (ref "IC17") (pin "6") (pinfunction "I6_6") (pintype "bidirectional"))
    )
    (net (code "161") (name "unconnected-(IC17-I7-Pad7)") (class "Default")
      (node (ref "IC17") (pin "7") (pinfunction "I7_7") (pintype "bidirectional"))
    )
    (net (code "162") (name "unconnected-(IC17-O4-Pad13)") (class "Default")
      (node (ref "IC17") (pin "13") (pinfunction "O4_13") (pintype "bidirectional"))
    )
    (net (code "163") (name "unconnected-(IC17-O5-Pad12)") (class "Default")
      (node (ref "IC17") (pin "12") (pinfunction "O5_12") (pintype "bidirectional"))
    )
    (net (code "164") (name "unconnected-(IC17-O6-Pad11)") (class "Default")
      (node (ref "IC17") (pin "11") (pinfunction "O6_11") (pintype "bidirectional"))
    )
    (net (code "165") (name "unconnected-(IC17-O7-Pad10)") (class "Default")
      (node (ref "IC17") (pin "10") (pinfunction "O7_10") (pintype "bidirectional"))
    )
    (net (code "166") (name "unconnected-(IC18-Y0-Pad15)") (class "Default")
      (node (ref "IC18") (pin "15") (pinfunction "Y0_15") (pintype "bidirectional"))
    )
    (net (code "167") (name "unconnected-(IC19-Y0-Pad15)") (class "Default")
      (node (ref "IC19") (pin "15") (pinfunction "Y0_15") (pintype "bidirectional"))
    )
    (net (code "168") (name "unconnected-(IC20-Y0-Pad15)") (class "Default")
      (node (ref "IC20") (pin "15") (pinfunction "Y0_15") (pintype "bidirectional"))
    )
    (net (code "169") (name "unconnected-(J1-NC1-PadP$8)") (class "Default")
      (node (ref "J1") (pin "P$8") (pinfunction "NC1_P$8") (pintype "bidirectional"))
    )
    (net (code "170") (name "unconnected-(J1-NC2-PadP$28)") (class "Default")
      (node (ref "J1") (pin "P$28") (pinfunction "NC2_P$28") (pintype "bidirectional"))
    )
    (net (code "171") (name "unconnected-(MCU1-RESET-Pad22)") (class "Default")
      (node (ref "MCU1") (pin "22") (pinfunction "RESET_22") (pintype "bidirectional"))
    )
    (net (code "172") (name "unconnected-(MCU1-RXI-Pad2)") (class "Default")
      (node (ref "MCU1") (pin "2") (pinfunction "RXI_2") (pintype "bidirectional"))
    )
    (net (code "173") (name "unconnected-(MCU1-TXO-Pad1)") (class "Default")
      (node (ref "MCU1") (pin "1") (pinfunction "TXO_1") (pintype "bidirectional"))
    )
  )
)
